# pc_vl53l0c_brk.net
KiCad netlist of a schematic drawn in EAGLE
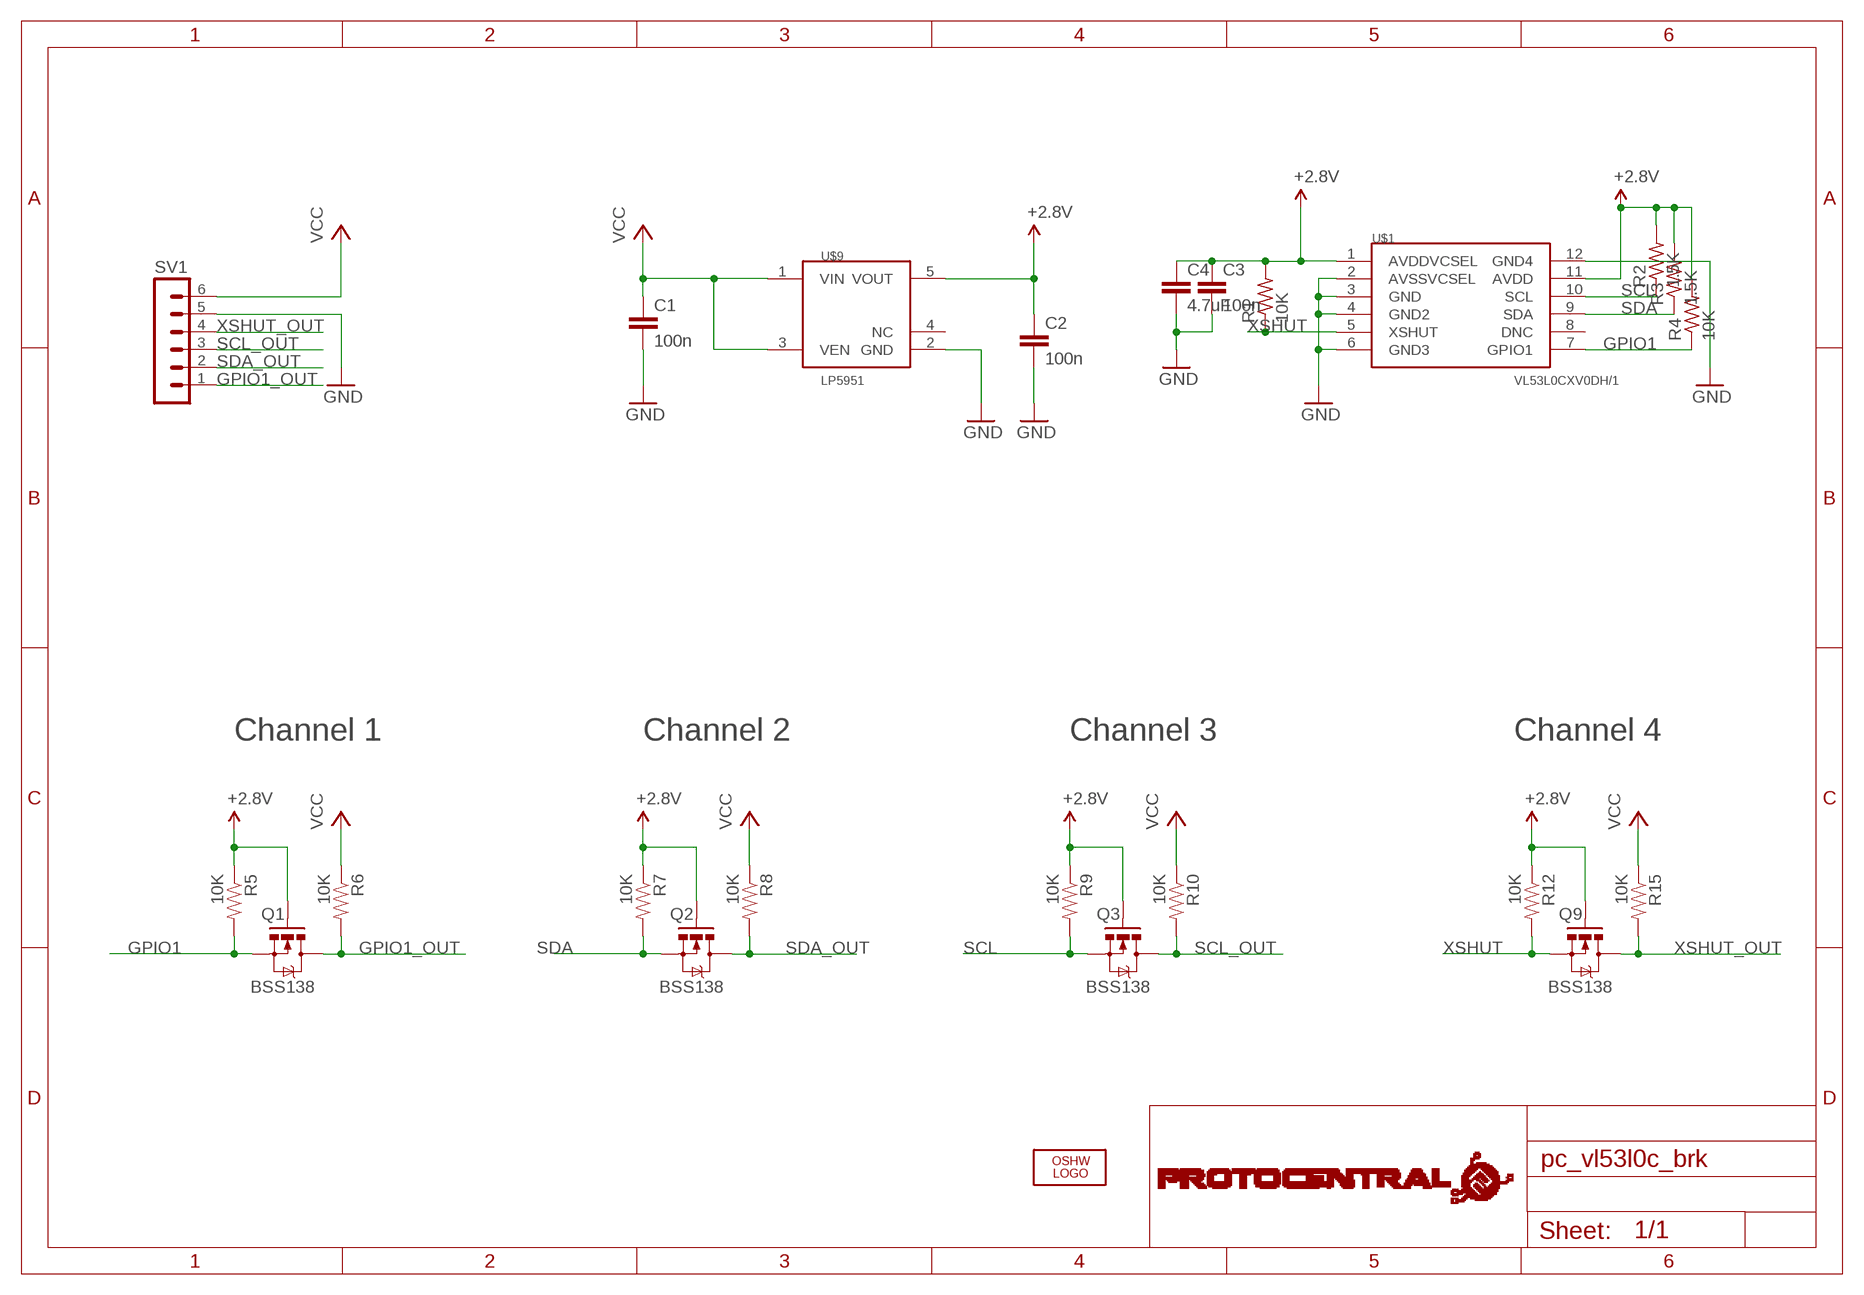
[diagram p0: schematic, sheet 1]

(export (version "E")
  (design (tool "Eeschema 10.0.6"))
  (components
    (comp (ref "C1")
      (value "100n")
      (footprint "eagle-import:C0402")
      (libsource (lib "eagle-import") (part "C-EUC0402"))
    )
    (comp (ref "C2")
      (value "100n")
      (footprint "eagle-import:C0402")
      (libsource (lib "eagle-import") (part "C-EUC0402"))
    )
    (comp (ref "C3")
      (value "100n")
      (footprint "eagle-import:C0402")
      (libsource (lib "eagle-import") (part "C-EUC0402"))
    )
    (comp (ref "C4")
      (value "4.7uF")
      (footprint "eagle-import:C0402")
      (libsource (lib "eagle-import") (part "C-EUC0402"))
    )
    (comp (ref "LOGO2")
      (value "OSHW_LOGO_FILLX0100-NT")
      (footprint "eagle-import:OSHW_FILLX100_NOTEXT")
      (libsource (lib "eagle-import") (part "OSHW_LOGO_FILLX0100-NT"))
    )
    (comp (ref "Q1")
      (value "BSS138")
      (footprint "eagle-import:SOT23-3")
      (libsource (lib "eagle-import") (part "MOSFET-NCHANNELSMD"))
    )
    (comp (ref "Q2")
      (value "BSS138")
      (footprint "eagle-import:SOT23-3")
      (libsource (lib "eagle-import") (part "MOSFET-NCHANNELSMD"))
    )
    (comp (ref "Q3")
      (value "BSS138")
      (footprint "eagle-import:SOT23-3")
      (libsource (lib "eagle-import") (part "MOSFET-NCHANNELSMD"))
    )
    (comp (ref "Q9")
      (value "BSS138")
      (footprint "eagle-import:SOT23-3")
      (libsource (lib "eagle-import") (part "MOSFET-NCHANNELSMD"))
    )
    (comp (ref "R1")
      (value "10K")
      (footprint "eagle-import:R0805")
      (libsource (lib "eagle-import") (part "R-US_R0805"))
    )
    (comp (ref "R2")
      (value "1.5K")
      (footprint "eagle-import:R0805")
      (libsource (lib "eagle-import") (part "R-US_R0805"))
    )
    (comp (ref "R3")
      (value "1.5K")
      (footprint "eagle-import:R0805")
      (libsource (lib "eagle-import") (part "R-US_R0805"))
    )
    (comp (ref "R4")
      (value "10K")
      (footprint "eagle-import:R0805")
      (libsource (lib "eagle-import") (part "R-US_R0805"))
    )
    (comp (ref "R5")
      (value "10K")
      (footprint "eagle-import:0805")
      (libsource (lib "eagle-import") (part "RESISTOR0805-RES"))
    )
    (comp (ref "R6")
      (value "10K")
      (footprint "eagle-import:0805")
      (libsource (lib "eagle-import") (part "RESISTOR0805-RES"))
    )
    (comp (ref "R7")
      (value "10K")
      (footprint "eagle-import:0805")
      (libsource (lib "eagle-import") (part "RESISTOR0805-RES"))
    )
    (comp (ref "R8")
      (value "10K")
      (footprint "eagle-import:0805")
      (libsource (lib "eagle-import") (part "RESISTOR0805-RES"))
    )
    (comp (ref "R9")
      (value "10K")
      (footprint "eagle-import:0805")
      (libsource (lib "eagle-import") (part "RESISTOR0805-RES"))
    )
    (comp (ref "R10")
      (value "10K")
      (footprint "eagle-import:0805")
      (libsource (lib "eagle-import") (part "RESISTOR0805-RES"))
    )
    (comp (ref "R12")
      (value "10K")
      (footprint "eagle-import:0805")
      (libsource (lib "eagle-import") (part "RESISTOR0805-RES"))
    )
    (comp (ref "R15")
      (value "10K")
      (footprint "eagle-import:0805")
      (libsource (lib "eagle-import") (part "RESISTOR0805-RES"))
    )
    (comp (ref "SV1")
      (value "MA06-1")
      (footprint "eagle-import:MA06-1")
      (libsource (lib "eagle-import") (part "MA06-1"))
    )
    (comp (ref "U$1")
      (value "VL53L0CXV0DH/1")
      (footprint "eagle-import:LGA-12")
      (libsource (lib "eagle-import") (part "VL53L0CXV0DH/1"))
    )
    (comp (ref "U$9")
      (value "LP5951")
      (footprint "eagle-import:SC70-5")
      (libsource (lib "eagle-import") (part "LP5951"))
    )
    (comp (ref "U$10")
      (value "PROTY_LOGO_WITH_TEXT")
      (footprint "eagle-import:PROTY_WITH_TEXT")
      (libsource (lib "eagle-import") (part "PROTY_LOGO_WITH_TEXT"))
    )
  )
  (nets
    (net (code "1") (name "+2.8V") (class "Default")
      (node (ref "C2") (pin "1") (pinfunction "1_1") (pintype "passive"))
      (node (ref "C3") (pin "1") (pinfunction "1_1") (pintype "passive"))
      (node (ref "C4") (pin "1") (pinfunction "1_1") (pintype "passive"))
      (node (ref "Q1") (pin "1") (pinfunction "G_1") (pintype "passive"))
      (node (ref "Q2") (pin "1") (pinfunction "G_1") (pintype "passive"))
      (node (ref "Q3") (pin "1") (pinfunction "G_1") (pintype "passive"))
      (node (ref "Q9") (pin "1") (pinfunction "G_1") (pintype "passive"))
      (node (ref "R1") (pin "2") (pinfunction "2_2") (pintype "passive"))
      (node (ref "R12") (pin "1") (pinfunction "1_1") (pintype "passive"))
      (node (ref "R2") (pin "2") (pinfunction "2_2") (pintype "passive"))
      (node (ref "R3") (pin "2") (pinfunction "2_2") (pintype "passive"))
      (node (ref "R4") (pin "2") (pinfunction "2_2") (pintype "passive"))
      (node (ref "R5") (pin "1") (pinfunction "1_1") (pintype "passive"))
      (node (ref "R7") (pin "1") (pinfunction "1_1") (pintype "passive"))
      (node (ref "R9") (pin "1") (pinfunction "1_1") (pintype "passive"))
      (node (ref "U$1") (pin "1") (pinfunction "AVDDVCSEL_1") (pintype "bidirectional"))
      (node (ref "U$1") (pin "11") (pinfunction "AVDD_11") (pintype "bidirectional"))
      (node (ref "U$9") (pin "5") (pinfunction "VOUT_5") (pintype "bidirectional"))
    )
    (net (code "2") (name "/GPIO1") (class "Default")
      (node (ref "Q1") (pin "2") (pinfunction "S_2") (pintype "passive"))
      (node (ref "R4") (pin "1") (pinfunction "1_1") (pintype "passive"))
      (node (ref "R5") (pin "2") (pinfunction "2_2") (pintype "passive"))
      (node (ref "U$1") (pin "7") (pinfunction "GPIO1_7") (pintype "bidirectional"))
    )
    (net (code "3") (name "/GPIO1_OUT") (class "Default")
      (node (ref "Q1") (pin "3") (pinfunction "D_3") (pintype "passive"))
      (node (ref "R6") (pin "2") (pinfunction "2_2") (pintype "passive"))
      (node (ref "SV1") (pin "1") (pinfunction "1_1") (pintype "passive"))
    )
    (net (code "4") (name "/SCL") (class "Default")
      (node (ref "Q3") (pin "2") (pinfunction "S_2") (pintype "passive"))
      (node (ref "R2") (pin "1") (pinfunction "1_1") (pintype "passive"))
      (node (ref "R9") (pin "2") (pinfunction "2_2") (pintype "passive"))
      (node (ref "U$1") (pin "10") (pinfunction "SCL_10") (pintype "bidirectional"))
    )
    (net (code "5") (name "/SCL_OUT") (class "Default")
      (node (ref "Q3") (pin "3") (pinfunction "D_3") (pintype "passive"))
      (node (ref "R10") (pin "2") (pinfunction "2_2") (pintype "passive"))
      (node (ref "SV1") (pin "3") (pinfunction "3_3") (pintype "passive"))
    )
    (net (code "6") (name "/SDA") (class "Default")
      (node (ref "Q2") (pin "2") (pinfunction "S_2") (pintype "passive"))
      (node (ref "R3") (pin "1") (pinfunction "1_1") (pintype "passive"))
      (node (ref "R7") (pin "2") (pinfunction "2_2") (pintype "passive"))
      (node (ref "U$1") (pin "9") (pinfunction "SDA_9") (pintype "bidirectional"))
    )
    (net (code "7") (name "/SDA_OUT") (class "Default")
      (node (ref "Q2") (pin "3") (pinfunction "D_3") (pintype "passive"))
      (node (ref "R8") (pin "2") (pinfunction "2_2") (pintype "passive"))
      (node (ref "SV1") (pin "2") (pinfunction "2_2") (pintype "passive"))
    )
    (net (code "8") (name "/XSHUT") (class "Default")
      (node (ref "Q9") (pin "2") (pinfunction "S_2") (pintype "passive"))
      (node (ref "R1") (pin "1") (pinfunction "1_1") (pintype "passive"))
      (node (ref "R12") (pin "2") (pinfunction "2_2") (pintype "passive"))
      (node (ref "U$1") (pin "5") (pinfunction "XSHUT_5") (pintype "bidirectional"))
    )
    (net (code "9") (name "/XSHUT_OUT") (class "Default")
      (node (ref "Q9") (pin "3") (pinfunction "D_3") (pintype "passive"))
      (node (ref "R15") (pin "2") (pinfunction "2_2") (pintype "passive"))
      (node (ref "SV1") (pin "4") (pinfunction "4_4") (pintype "passive"))
    )
    (net (code "10") (name "GND") (class "Default")
      (node (ref "C1") (pin "2") (pinfunction "2_2") (pintype "passive"))
      (node (ref "C2") (pin "2") (pinfunction "2_2") (pintype "passive"))
      (node (ref "C3") (pin "2") (pinfunction "2_2") (pintype "passive"))
      (node (ref "C4") (pin "2") (pinfunction "2_2") (pintype "passive"))
      (node (ref "SV1") (pin "5") (pinfunction "5_5") (pintype "passive"))
      (node (ref "U$1") (pin "12") (pinfunction "GND4_12") (pintype "bidirectional"))
      (node (ref "U$1") (pin "2") (pinfunction "AVSSVCSEL_2") (pintype "bidirectional"))
      (node (ref "U$1") (pin "3") (pinfunction "GND_3") (pintype "bidirectional"))
      (node (ref "U$1") (pin "4") (pinfunction "GND2_4") (pintype "bidirectional"))
      (node (ref "U$1") (pin "6") (pinfunction "GND3_6") (pintype "bidirectional"))
      (node (ref "U$9") (pin "2") (pinfunction "GND_2") (pintype "bidirectional"))
    )
    (net (code "11") (name "VCC") (class "Default")
      (node (ref "C1") (pin "1") (pinfunction "1_1") (pintype "passive"))
      (node (ref "R10") (pin "1") (pinfunction "1_1") (pintype "passive"))
      (node (ref "R15") (pin "1") (pinfunction "1_1") (pintype "passive"))
      (node (ref "R6") (pin "1") (pinfunction "1_1") (pintype "passive"))
      (node (ref "R8") (pin "1") (pinfunction "1_1") (pintype "passive"))
      (node (ref "SV1") (pin "6") (pinfunction "6_6") (pintype "passive"))
      (node (ref "U$9") (pin "1") (pinfunction "VIN_1") (pintype "bidirectional"))
      (node (ref "U$9") (pin "3") (pinfunction "VEN_3") (pintype "bidirectional"))
    )
    (net (code "12") (name "unconnected-(U$1-DNC-Pad8)") (class "Default")
      (node (ref "U$1") (pin "8") (pinfunction "DNC_8") (pintype "bidirectional"))
    )
    (net (code "13") (name "unconnected-(U$9-NC-Pad4)") (class "Default")
      (node (ref "U$9") (pin "4") (pinfunction "NC_4") (pintype "bidirectional"))
    )
  )
)
